# OptronV7_PCB.net
KiCad netlist of a schematic drawn in EAGLE
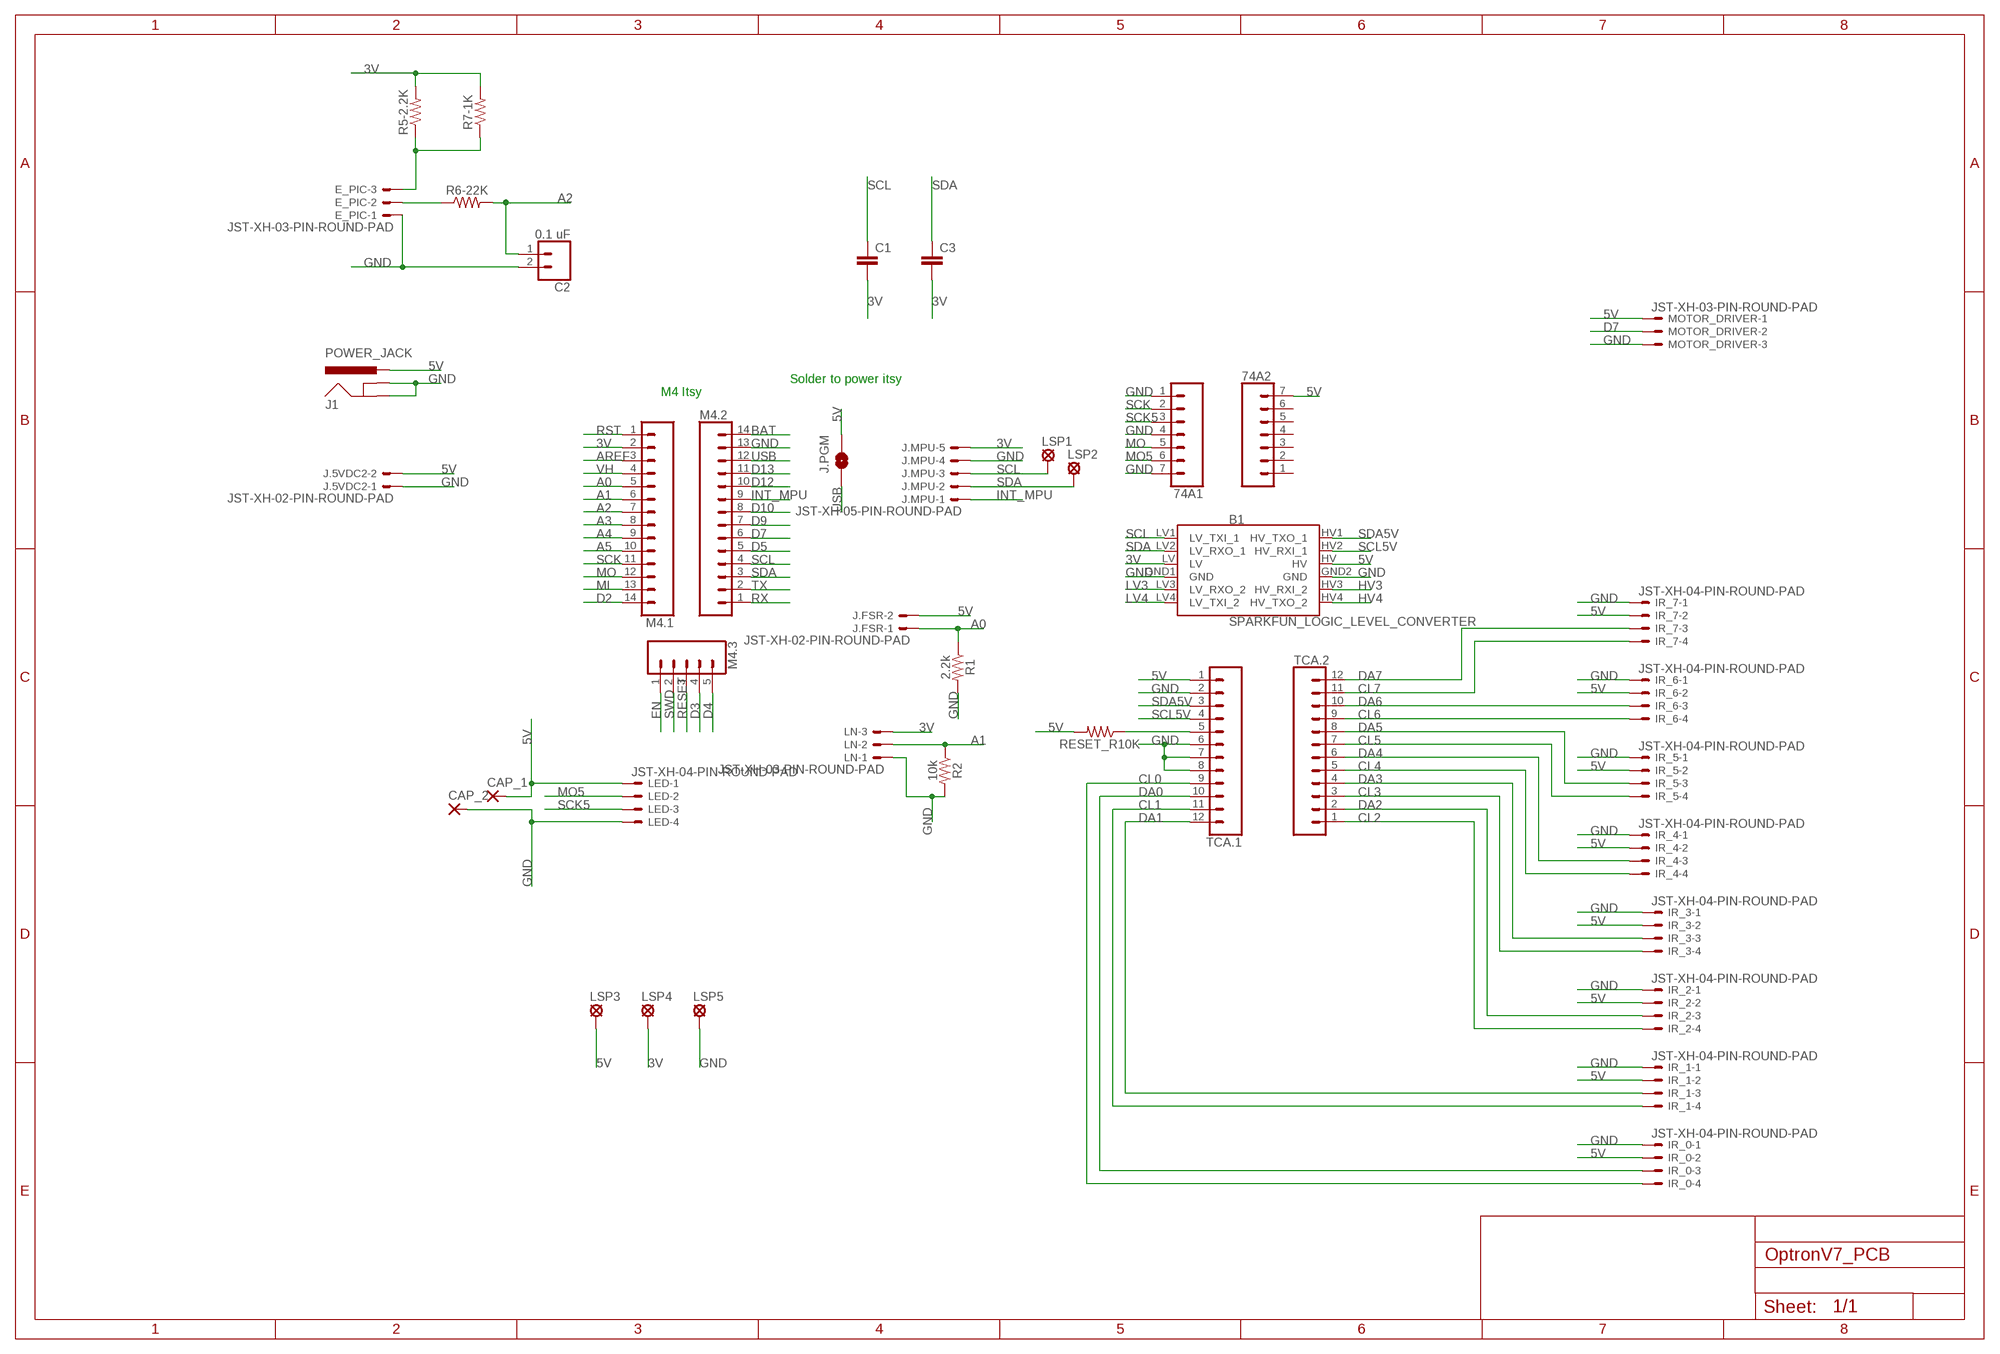
[diagram p0: schematic, sheet 1]

(export (version "E")
  (design (tool "Eeschema 10.0.6"))
  (components
    (comp (ref "74A1")
      (value "CONN_07")
      (footprint "eagle-import:1X07")
      (libsource (lib "eagle-import") (part "CONN_07"))
    )
    (comp (ref "74A2")
      (value "CONN_07")
      (footprint "eagle-import:1X07")
      (libsource (lib "eagle-import") (part "CONN_07"))
    )
    (comp (ref "B1")
      (value "SPARKFUN_LOGIC_LEVEL_CONVERTER")
      (footprint "eagle-import:SPARKFUN_LOGIC_LEVEL_CONVERTER")
      (libsource (lib "eagle-import") (part "SPARKFUN_LOGIC_LEVEL_CONVERTER"))
    )
    (comp (ref "C1")
      (value "C5/2.5")
      (footprint "eagle-import:C5B2.5")
      (libsource (lib "eagle-import") (part "C5/2.5"))
    )
    (comp (ref "C2")
      (value "0.1 uF")
      (footprint "eagle-import:1X02")
      (libsource (lib "eagle-import") (part "CONN_02"))
    )
    (comp (ref "C3")
      (value "C5/2.5")
      (footprint "eagle-import:C5B2.5")
      (libsource (lib "eagle-import") (part "C5/2.5"))
    )
    (comp (ref "CAP_1")
      (value "1,6/0,8")
      (footprint "eagle-import:1,6_0,8")
      (libsource (lib "eagle-import") (part "1,6/0,8"))
    )
    (comp (ref "CAP_2")
      (value "1,6/0,8")
      (footprint "eagle-import:1,6_0,8")
      (libsource (lib "eagle-import") (part "1,6/0,8"))
    )
    (comp (ref "E_PIC")
      (value "JST-XH-03-PIN-ROUND-PAD")
      (footprint "eagle-import:JST-XH-03-PACKAGE-ROUND-PAD")
      (libsource (lib "eagle-import") (part "JST-XH-03-PIN-ROUND-PAD"))
    )
    (comp (ref "IR_0")
      (value "JST-XH-04-PIN-ROUND-PAD")
      (footprint "eagle-import:JST-XH-04-PACKAGE-ROUND-PAD")
      (libsource (lib "eagle-import") (part "JST-XH-04-PIN-ROUND-PAD"))
    )
    (comp (ref "IR_1")
      (value "JST-XH-04-PIN-ROUND-PAD")
      (footprint "eagle-import:JST-XH-04-PACKAGE-ROUND-PAD")
      (libsource (lib "eagle-import") (part "JST-XH-04-PIN-ROUND-PAD"))
    )
    (comp (ref "IR_2")
      (value "JST-XH-04-PIN-ROUND-PAD")
      (footprint "eagle-import:JST-XH-04-PACKAGE-ROUND-PAD")
      (libsource (lib "eagle-import") (part "JST-XH-04-PIN-ROUND-PAD"))
    )
    (comp (ref "IR_3")
      (value "JST-XH-04-PIN-ROUND-PAD")
      (footprint "eagle-import:JST-XH-04-PACKAGE-ROUND-PAD")
      (libsource (lib "eagle-import") (part "JST-XH-04-PIN-ROUND-PAD"))
    )
    (comp (ref "IR_4")
      (value "JST-XH-04-PIN-ROUND-PAD")
      (footprint "eagle-import:JST-XH-04-PACKAGE-ROUND-PAD")
      (libsource (lib "eagle-import") (part "JST-XH-04-PIN-ROUND-PAD"))
    )
    (comp (ref "IR_5")
      (value "JST-XH-04-PIN-ROUND-PAD")
      (footprint "eagle-import:JST-XH-04-PACKAGE-ROUND-PAD")
      (libsource (lib "eagle-import") (part "JST-XH-04-PIN-ROUND-PAD"))
    )
    (comp (ref "IR_6")
      (value "JST-XH-04-PIN-ROUND-PAD")
      (footprint "eagle-import:JST-XH-04-PACKAGE-ROUND-PAD")
      (libsource (lib "eagle-import") (part "JST-XH-04-PIN-ROUND-PAD"))
    )
    (comp (ref "IR_7")
      (value "JST-XH-04-PIN-ROUND-PAD")
      (footprint "eagle-import:JST-XH-04-PACKAGE-ROUND-PAD")
      (libsource (lib "eagle-import") (part "JST-XH-04-PIN-ROUND-PAD"))
    )
    (comp (ref "J.5VDC2")
      (value "JST-XH-02-PIN-ROUND-PAD")
      (footprint "eagle-import:JST-XH-02-PACKAGE-ROUND-PAD")
      (libsource (lib "eagle-import") (part "JST-XH-02-PIN-ROUND-PAD"))
    )
    (comp (ref "J.FSR")
      (value "JST-XH-02-PIN-ROUND-PAD")
      (footprint "eagle-import:JST-XH-02-PACKAGE-ROUND-PAD")
      (libsource (lib "eagle-import") (part "JST-XH-02-PIN-ROUND-PAD"))
    )
    (comp (ref "J.MPU")
      (value "JST-XH-05-PIN-ROUND-PAD")
      (footprint "eagle-import:JST-XH-05-PACKAGE-ROUND-PAD")
      (libsource (lib "eagle-import") (part "JST-XH-05-PIN-ROUND-PAD"))
    )
    (comp (ref "J.PGM")
      (value "JUMPER-SMT_2_NO_NO-SILK")
      (footprint "eagle-import:SMT-JUMPER_2_NO_NO-SILK")
      (libsource (lib "eagle-import") (part "JUMPER-SMT_2_NO_NO-SILK"))
    )
    (comp (ref "J1")
      (value "POWER_JACK")
      (footprint "eagle-import:POWER_JACK_PTH")
      (libsource (lib "eagle-import") (part "POWER_JACK"))
    )
    (comp (ref "LED")
      (value "JST-XH-04-PIN-ROUND-PAD")
      (footprint "eagle-import:JST-XH-04-PACKAGE-ROUND-PAD")
      (libsource (lib "eagle-import") (part "JST-XH-04-PIN-ROUND-PAD"))
    )
    (comp (ref "LN")
      (value "JST-XH-03-PIN-ROUND-PAD")
      (footprint "eagle-import:JST-XH-03-PACKAGE-ROUND-PAD")
      (libsource (lib "eagle-import") (part "JST-XH-03-PIN-ROUND-PAD"))
    )
    (comp (ref "LSP1")
      (value "MCS08")
      (footprint "eagle-import:MCS08")
      (libsource (lib "eagle-import") (part "MCS08"))
    )
    (comp (ref "LSP2")
      (value "MCS08")
      (footprint "eagle-import:MCS08")
      (libsource (lib "eagle-import") (part "MCS08"))
    )
    (comp (ref "LSP3")
      (value "MCS08")
      (footprint "eagle-import:MCS08")
      (libsource (lib "eagle-import") (part "MCS08"))
    )
    (comp (ref "LSP4")
      (value "MCS08")
      (footprint "eagle-import:MCS08")
      (libsource (lib "eagle-import") (part "MCS08"))
    )
    (comp (ref "LSP5")
      (value "MCS08")
      (footprint "eagle-import:MCS08")
      (libsource (lib "eagle-import") (part "MCS08"))
    )
    (comp (ref "M4.1")
      (value "CONN_14")
      (footprint "eagle-import:1X14")
      (libsource (lib "eagle-import") (part "CONN_14"))
    )
    (comp (ref "M4.2")
      (value "CONN_14")
      (footprint "eagle-import:1X14")
      (libsource (lib "eagle-import") (part "CONN_14"))
    )
    (comp (ref "M4.3")
      (value "CONN_05")
      (footprint "eagle-import:1X05")
      (libsource (lib "eagle-import") (part "CONN_05"))
    )
    (comp (ref "MOTOR_DRIVER")
      (value "JST-XH-03-PIN-ROUND-PAD")
      (footprint "eagle-import:JST-XH-03-PACKAGE-ROUND-PAD")
      (libsource (lib "eagle-import") (part "JST-XH-03-PIN-ROUND-PAD"))
    )
    (comp (ref "R1")
      (value "2.2k")
      (footprint "eagle-import:AXIAL-0.3")
      (libsource (lib "eagle-import") (part "10KOHM-HORIZ-1/4W-5%"))
    )
    (comp (ref "R2")
      (value "10k")
      (footprint "eagle-import:AXIAL-0.3")
      (libsource (lib "eagle-import") (part "10KOHM-HORIZ-1/4W-5%"))
    )
    (comp (ref "R5-2.2K")
      (value "RESISTORAXIAL-0.3")
      (footprint "eagle-import:AXIAL-0.3")
      (libsource (lib "eagle-import") (part "RESISTORAXIAL-0.3"))
    )
    (comp (ref "R6-22K")
      (value "RESISTORAXIAL-0.3")
      (footprint "eagle-import:AXIAL-0.3")
      (libsource (lib "eagle-import") (part "RESISTORAXIAL-0.3"))
    )
    (comp (ref "R7-1K")
      (value "RESISTORAXIAL-0.3")
      (footprint "eagle-import:AXIAL-0.3")
      (libsource (lib "eagle-import") (part "RESISTORAXIAL-0.3"))
    )
    (comp (ref "RESET_R10K")
      (value "RESISTORAXIAL-0.3")
      (footprint "eagle-import:AXIAL-0.3")
      (libsource (lib "eagle-import") (part "RESISTORAXIAL-0.3"))
    )
    (comp (ref "TCA.1")
      (value "CONN_12")
      (footprint "eagle-import:1X12")
      (libsource (lib "eagle-import") (part "CONN_12"))
    )
    (comp (ref "TCA.2")
      (value "CONN_12")
      (footprint "eagle-import:1X12")
      (libsource (lib "eagle-import") (part "CONN_12"))
    )
  )
  (nets
    (net (code "1") (name "/3V") (class "Default")
      (node (ref "B1") (pin "LV") (pinfunction "LV_LV") (pintype "power_in"))
      (node (ref "C1") (pin "2") (pinfunction "2_2") (pintype "passive"))
      (node (ref "C3") (pin "2") (pinfunction "2_2") (pintype "passive"))
      (node (ref "J.MPU") (pin "5") (pinfunction "S_5") (pintype "passive"))
      (node (ref "LN") (pin "3") (pinfunction "S_3") (pintype "passive"))
      (node (ref "LSP4") (pin "MP") (pinfunction "MP_MP") (pintype "passive"))
      (node (ref "M4.1") (pin "2") (pinfunction "2_2") (pintype "passive"))
      (node (ref "R5-2.2K") (pin "P$2") (pinfunction "2_P$2") (pintype "passive"))
      (node (ref "R7-1K") (pin "P$2") (pinfunction "2_P$2") (pintype "passive"))
    )
    (net (code "2") (name "/5V") (class "Default")
      (node (ref "74A2") (pin "7") (pinfunction "7_7") (pintype "passive"))
      (node (ref "B1") (pin "HV") (pinfunction "HV_HV") (pintype "power_in"))
      (node (ref "CAP_1") (pin "1") (pinfunction "P_1") (pintype "passive"))
      (node (ref "IR_0") (pin "2") (pinfunction "S_2") (pintype "passive"))
      (node (ref "IR_1") (pin "2") (pinfunction "S_2") (pintype "passive"))
      (node (ref "IR_2") (pin "2") (pinfunction "S_2") (pintype "passive"))
      (node (ref "IR_3") (pin "2") (pinfunction "S_2") (pintype "passive"))
      (node (ref "IR_4") (pin "2") (pinfunction "S_2") (pintype "passive"))
      (node (ref "IR_5") (pin "2") (pinfunction "S_2") (pintype "passive"))
      (node (ref "IR_6") (pin "2") (pinfunction "S_2") (pintype "passive"))
      (node (ref "IR_7") (pin "2") (pinfunction "S_2") (pintype "passive"))
      (node (ref "J.5VDC2") (pin "2") (pinfunction "S_2") (pintype "passive"))
      (node (ref "J.FSR") (pin "2") (pinfunction "S_2") (pintype "passive"))
      (node (ref "J.PGM") (pin "2") (pinfunction "2_2") (pintype "passive"))
      (node (ref "J1") (pin "PWR") (pinfunction "PWR_PWR") (pintype "bidirectional"))
      (node (ref "LED") (pin "1") (pinfunction "S_1") (pintype "passive"))
      (node (ref "LSP3") (pin "MP") (pinfunction "MP_MP") (pintype "passive"))
      (node (ref "MOTOR_DRIVER") (pin "1") (pinfunction "S_1") (pintype "passive"))
      (node (ref "RESET_R10K") (pin "P$2") (pinfunction "2_P$2") (pintype "passive"))
      (node (ref "TCA.1") (pin "1") (pinfunction "1_1") (pintype "passive"))
    )
    (net (code "3") (name "/A0") (class "Default")
      (node (ref "J.FSR") (pin "1") (pinfunction "S_1") (pintype "passive"))
      (node (ref "M4.1") (pin "5") (pinfunction "5_5") (pintype "passive"))
      (node (ref "R1") (pin "P$1") (pinfunction "1_P$1") (pintype "passive"))
    )
    (net (code "4") (name "/A1") (class "Default")
      (node (ref "LN") (pin "2") (pinfunction "S_2") (pintype "passive"))
      (node (ref "M4.1") (pin "6") (pinfunction "6_6") (pintype "passive"))
      (node (ref "R2") (pin "P$1") (pinfunction "1_P$1") (pintype "passive"))
    )
    (net (code "5") (name "/A2") (class "Default")
      (node (ref "C2") (pin "1") (pinfunction "1_1") (pintype "passive"))
      (node (ref "M4.1") (pin "7") (pinfunction "7_7") (pintype "passive"))
      (node (ref "R6-22K") (pin "P$2") (pinfunction "2_P$2") (pintype "passive"))
    )
    (net (code "6") (name "/A3") (class "Default")
      (node (ref "M4.1") (pin "8") (pinfunction "8_8") (pintype "passive"))
    )
    (net (code "7") (name "/A4") (class "Default")
      (node (ref "M4.1") (pin "9") (pinfunction "9_9") (pintype "passive"))
    )
    (net (code "8") (name "/A5") (class "Default")
      (node (ref "M4.1") (pin "10") (pinfunction "10_10") (pintype "passive"))
    )
    (net (code "9") (name "/AREF") (class "Default")
      (node (ref "M4.1") (pin "3") (pinfunction "3_3") (pintype "passive"))
    )
    (net (code "10") (name "/BAT") (class "Default")
      (node (ref "M4.2") (pin "14") (pinfunction "14_14") (pintype "passive"))
    )
    (net (code "11") (name "/CL0") (class "Default")
      (node (ref "IR_0") (pin "4") (pinfunction "S_4") (pintype "passive"))
      (node (ref "TCA.1") (pin "9") (pinfunction "9_9") (pintype "passive"))
    )
    (net (code "12") (name "/CL1") (class "Default")
      (node (ref "IR_1") (pin "4") (pinfunction "S_4") (pintype "passive"))
      (node (ref "TCA.1") (pin "11") (pinfunction "11_11") (pintype "passive"))
    )
    (net (code "13") (name "/CL2") (class "Default")
      (node (ref "IR_2") (pin "4") (pinfunction "S_4") (pintype "passive"))
      (node (ref "TCA.2") (pin "1") (pinfunction "1_1") (pintype "passive"))
    )
    (net (code "14") (name "/CL3") (class "Default")
      (node (ref "IR_3") (pin "4") (pinfunction "S_4") (pintype "passive"))
      (node (ref "TCA.2") (pin "3") (pinfunction "3_3") (pintype "passive"))
    )
    (net (code "15") (name "/CL4") (class "Default")
      (node (ref "IR_4") (pin "4") (pinfunction "S_4") (pintype "passive"))
      (node (ref "TCA.2") (pin "5") (pinfunction "5_5") (pintype "passive"))
    )
    (net (code "16") (name "/CL5") (class "Default")
      (node (ref "IR_5") (pin "4") (pinfunction "S_4") (pintype "passive"))
      (node (ref "TCA.2") (pin "7") (pinfunction "7_7") (pintype "passive"))
    )
    (net (code "17") (name "/CL6") (class "Default")
      (node (ref "IR_6") (pin "4") (pinfunction "S_4") (pintype "passive"))
      (node (ref "TCA.2") (pin "9") (pinfunction "9_9") (pintype "passive"))
    )
    (net (code "18") (name "/CL7") (class "Default")
      (node (ref "IR_7") (pin "4") (pinfunction "S_4") (pintype "passive"))
      (node (ref "TCA.2") (pin "11") (pinfunction "11_11") (pintype "passive"))
    )
    (net (code "19") (name "/D2") (class "Default")
      (node (ref "M4.1") (pin "14") (pinfunction "14_14") (pintype "passive"))
    )
    (net (code "20") (name "/D3") (class "Default")
      (node (ref "M4.3") (pin "4") (pinfunction "4_4") (pintype "passive"))
    )
    (net (code "21") (name "/D4") (class "Default")
      (node (ref "M4.3") (pin "5") (pinfunction "5_5") (pintype "passive"))
    )
    (net (code "22") (name "/D5") (class "Default")
      (node (ref "M4.2") (pin "5") (pinfunction "5_5") (pintype "passive"))
    )
    (net (code "23") (name "/D7") (class "Default")
      (node (ref "M4.2") (pin "6") (pinfunction "6_6") (pintype "passive"))
      (node (ref "MOTOR_DRIVER") (pin "2") (pinfunction "S_2") (pintype "passive"))
    )
    (net (code "24") (name "/D9") (class "Default")
      (node (ref "M4.2") (pin "7") (pinfunction "7_7") (pintype "passive"))
    )
    (net (code "25") (name "/D10") (class "Default")
      (node (ref "M4.2") (pin "8") (pinfunction "8_8") (pintype "passive"))
    )
    (net (code "26") (name "/D12") (class "Default")
      (node (ref "M4.2") (pin "10") (pinfunction "10_10") (pintype "passive"))
    )
    (net (code "27") (name "/D13") (class "Default")
      (node (ref "M4.2") (pin "11") (pinfunction "11_11") (pintype "passive"))
    )
    (net (code "28") (name "/DA0") (class "Default")
      (node (ref "IR_0") (pin "3") (pinfunction "S_3") (pintype "passive"))
      (node (ref "TCA.1") (pin "10") (pinfunction "10_10") (pintype "passive"))
    )
    (net (code "29") (name "/DA1") (class "Default")
      (node (ref "IR_1") (pin "3") (pinfunction "S_3") (pintype "passive"))
      (node (ref "TCA.1") (pin "12") (pinfunction "12_12") (pintype "passive"))
    )
    (net (code "30") (name "/DA2") (class "Default")
      (node (ref "IR_2") (pin "3") (pinfunction "S_3") (pintype "passive"))
      (node (ref "TCA.2") (pin "2") (pinfunction "2_2") (pintype "passive"))
    )
    (net (code "31") (name "/DA3") (class "Default")
      (node (ref "IR_3") (pin "3") (pinfunction "S_3") (pintype "passive"))
      (node (ref "TCA.2") (pin "4") (pinfunction "4_4") (pintype "passive"))
    )
    (net (code "32") (name "/DA4") (class "Default")
      (node (ref "IR_4") (pin "3") (pinfunction "S_3") (pintype "passive"))
      (node (ref "TCA.2") (pin "6") (pinfunction "6_6") (pintype "passive"))
    )
    (net (code "33") (name "/DA5") (class "Default")
      (node (ref "IR_5") (pin "3") (pinfunction "S_3") (pintype "passive"))
      (node (ref "TCA.2") (pin "8") (pinfunction "8_8") (pintype "passive"))
    )
    (net (code "34") (name "/DA6") (class "Default")
      (node (ref "IR_6") (pin "3") (pinfunction "S_3") (pintype "passive"))
      (node (ref "TCA.2") (pin "10") (pinfunction "10_10") (pintype "passive"))
    )
    (net (code "35") (name "/DA7") (class "Default")
      (node (ref "IR_7") (pin "3") (pinfunction "S_3") (pintype "passive"))
      (node (ref "TCA.2") (pin "12") (pinfunction "12_12") (pintype "passive"))
    )
    (net (code "36") (name "/EN") (class "Default")
      (node (ref "M4.3") (pin "1") (pinfunction "1_1") (pintype "passive"))
    )
    (net (code "37") (name "/GND") (class "Default")
      (node (ref "74A1") (pin "1") (pinfunction "1_1") (pintype "passive"))
      (node (ref "74A1") (pin "4") (pinfunction "4_4") (pintype "passive"))
      (node (ref "74A1") (pin "7") (pinfunction "7_7") (pintype "passive"))
      (node (ref "B1") (pin "GND1") (pinfunction "GND_GND1") (pintype "power_in"))
      (node (ref "B1") (pin "GND2") (pinfunction "GND_GND2") (pintype "power_in"))
      (node (ref "C2") (pin "2") (pinfunction "2_2") (pintype "passive"))
      (node (ref "CAP_2") (pin "1") (pinfunction "P_1") (pintype "passive"))
      (node (ref "E_PIC") (pin "1") (pinfunction "S_1") (pintype "passive"))
      (node (ref "IR_0") (pin "1") (pinfunction "S_1") (pintype "passive"))
      (node (ref "IR_1") (pin "1") (pinfunction "S_1") (pintype "passive"))
      (node (ref "IR_2") (pin "1") (pinfunction "S_1") (pintype "passive"))
      (node (ref "IR_3") (pin "1") (pinfunction "S_1") (pintype "passive"))
      (node (ref "IR_4") (pin "1") (pinfunction "S_1") (pintype "passive"))
      (node (ref "IR_5") (pin "1") (pinfunction "S_1") (pintype "passive"))
      (node (ref "IR_6") (pin "1") (pinfunction "S_1") (pintype "passive"))
      (node (ref "IR_7") (pin "1") (pinfunction "S_1") (pintype "passive"))
      (node (ref "J.5VDC2") (pin "1") (pinfunction "S_1") (pintype "passive"))
      (node (ref "J.MPU") (pin "4") (pinfunction "S_4") (pintype "passive"))
      (node (ref "J1") (pin "GND") (pinfunction "GND_GND") (pintype "bidirectional"))
      (node (ref "J1") (pin "GNDBREAK") (pinfunction "GNDBREAK_GNDBREAK") (pintype "bidirectional"))
      (node (ref "LED") (pin "4") (pinfunction "S_4") (pintype "passive"))
      (node (ref "LN") (pin "1") (pinfunction "S_1") (pintype "passive"))
      (node (ref "LSP5") (pin "MP") (pinfunction "MP_MP") (pintype "passive"))
      (node (ref "M4.2") (pin "13") (pinfunction "13_13") (pintype "passive"))
      (node (ref "MOTOR_DRIVER") (pin "3") (pinfunction "S_3") (pintype "passive"))
      (node (ref "R1") (pin "P$2") (pinfunction "2_P$2") (pintype "passive"))
      (node (ref "R2") (pin "P$2") (pinfunction "2_P$2") (pintype "passive"))
      (node (ref "TCA.1") (pin "2") (pinfunction "2_2") (pintype "passive"))
      (node (ref "TCA.1") (pin "6") (pinfunction "6_6") (pintype "passive"))
      (node (ref "TCA.1") (pin "7") (pinfunction "7_7") (pintype "passive"))
      (node (ref "TCA.1") (pin "8") (pinfunction "8_8") (pintype "passive"))
    )
    (net (code "38") (name "/HV3") (class "Default")
      (node (ref "B1") (pin "HV3") (pinfunction "HV_RXI_2_HV3") (pintype "bidirectional"))
    )
    (net (code "39") (name "/HV4") (class "Default")
      (node (ref "B1") (pin "HV4") (pinfunction "HV_TXO_2_HV4") (pintype "bidirectional"))
    )
    (net (code "40") (name "/INT_MPU") (class "Default")
      (node (ref "J.MPU") (pin "1") (pinfunction "S_1") (pintype "passive"))
      (node (ref "M4.2") (pin "9") (pinfunction "9_9") (pintype "passive"))
    )
    (net (code "41") (name "/LV3") (class "Default")
      (node (ref "B1") (pin "LV3") (pinfunction "LV_RXO_2_LV3") (pintype "bidirectional"))
    )
    (net (code "42") (name "/LV4") (class "Default")
      (node (ref "B1") (pin "LV4") (pinfunction "LV_TXI_2_LV4") (pintype "bidirectional"))
    )
    (net (code "43") (name "/MI") (class "Default")
      (node (ref "M4.1") (pin "13") (pinfunction "13_13") (pintype "passive"))
    )
    (net (code "44") (name "/MO") (class "Default")
      (node (ref "74A1") (pin "5") (pinfunction "5_5") (pintype "passive"))
      (node (ref "M4.1") (pin "12") (pinfunction "12_12") (pintype "passive"))
    )
    (net (code "45") (name "/MO5") (class "Default")
      (node (ref "74A1") (pin "6") (pinfunction "6_6") (pintype "passive"))
      (node (ref "LED") (pin "2") (pinfunction "S_2") (pintype "passive"))
    )
    (net (code "46") (name "/RESET") (class "Default")
      (node (ref "M4.3") (pin "3") (pinfunction "3_3") (pintype "passive"))
    )
    (net (code "47") (name "/RST") (class "Default")
      (node (ref "M4.1") (pin "1") (pinfunction "1_1") (pintype "passive"))
    )
    (net (code "48") (name "/RX") (class "Default")
      (node (ref "M4.2") (pin "1") (pinfunction "1_1") (pintype "passive"))
    )
    (net (code "49") (name "/SCK") (class "Default")
      (node (ref "74A1") (pin "2") (pinfunction "2_2") (pintype "passive"))
      (node (ref "M4.1") (pin "11") (pinfunction "11_11") (pintype "passive"))
    )
    (net (code "50") (name "/SCK5") (class "Default")
      (node (ref "74A1") (pin "3") (pinfunction "3_3") (pintype "passive"))
      (node (ref "LED") (pin "3") (pinfunction "S_3") (pintype "passive"))
    )
    (net (code "51") (name "/SCL") (class "Default")
      (node (ref "B1") (pin "LV1") (pinfunction "LV_TXI_1_LV1") (pintype "bidirectional"))
      (node (ref "C1") (pin "1") (pinfunction "1_1") (pintype "passive"))
      (node (ref "J.MPU") (pin "3") (pinfunction "S_3") (pintype "passive"))
      (node (ref "LSP1") (pin "MP") (pinfunction "MP_MP") (pintype "passive"))
      (node (ref "M4.2") (pin "4") (pinfunction "4_4") (pintype "passive"))
    )
    (net (code "52") (name "/SCL5V") (class "Default")
      (node (ref "B1") (pin "HV2") (pinfunction "HV_RXI_1_HV2") (pintype "bidirectional"))
      (node (ref "TCA.1") (pin "4") (pinfunction "4_4") (pintype "passive"))
    )
    (net (code "53") (name "/SDA") (class "Default")
      (node (ref "B1") (pin "LV2") (pinfunction "LV_RXO_1_LV2") (pintype "bidirectional"))
      (node (ref "C3") (pin "1") (pinfunction "1_1") (pintype "passive"))
      (node (ref "J.MPU") (pin "2") (pinfunction "S_2") (pintype "passive"))
      (node (ref "LSP2") (pin "MP") (pinfunction "MP_MP") (pintype "passive"))
      (node (ref "M4.2") (pin "3") (pinfunction "3_3") (pintype "passive"))
    )
    (net (code "54") (name "/SDA5V") (class "Default")
      (node (ref "B1") (pin "HV1") (pinfunction "HV_TXO_1_HV1") (pintype "bidirectional"))
      (node (ref "TCA.1") (pin "3") (pinfunction "3_3") (pintype "passive"))
    )
    (net (code "55") (name "/SWD") (class "Default")
      (node (ref "M4.3") (pin "2") (pinfunction "2_2") (pintype "passive"))
    )
    (net (code "56") (name "/TX") (class "Default")
      (node (ref "M4.2") (pin "2") (pinfunction "2_2") (pintype "passive"))
    )
    (net (code "57") (name "/USB") (class "Default")
      (node (ref "J.PGM") (pin "1") (pinfunction "1_1") (pintype "passive"))
      (node (ref "M4.2") (pin "12") (pinfunction "12_12") (pintype "passive"))
    )
    (net (code "58") (name "/VH") (class "Default")
      (node (ref "M4.1") (pin "4") (pinfunction "4_4") (pintype "passive"))
    )
    (net (code "59") (name "Net-(E_PICB-S)") (class "Default")
      (node (ref "E_PIC") (pin "2") (pinfunction "S_2") (pintype "passive"))
      (node (ref "R6-22K") (pin "P$1") (pinfunction "1_P$1") (pintype "passive"))
    )
    (net (code "60") (name "Net-(E_PICC-S)") (class "Default")
      (node (ref "E_PIC") (pin "3") (pinfunction "S_3") (pintype "passive"))
      (node (ref "R5-2.2K") (pin "P$1") (pinfunction "1_P$1") (pintype "passive"))
      (node (ref "R7-1K") (pin "P$1") (pinfunction "1_P$1") (pintype "passive"))
    )
    (net (code "61") (name "Net-(RESET_R10K-1)") (class "Default")
      (node (ref "RESET_R10K") (pin "P$1") (pinfunction "1_P$1") (pintype "passive"))
      (node (ref "TCA.1") (pin "5") (pinfunction "5_5") (pintype "passive"))
    )
    (net (code "62") (name "unconnected-(74A2-Pad1)") (class "Default")
      (node (ref "74A2") (pin "1") (pinfunction "1_1") (pintype "passive"))
    )
    (net (code "63") (name "unconnected-(74A2-Pad2)") (class "Default")
      (node (ref "74A2") (pin "2") (pinfunction "2_2") (pintype "passive"))
    )
    (net (code "64") (name "unconnected-(74A2-Pad3)") (class "Default")
      (node (ref "74A2") (pin "3") (pinfunction "3_3") (pintype "passive"))
    )
    (net (code "65") (name "unconnected-(74A2-Pad4)") (class "Default")
      (node (ref "74A2") (pin "4") (pinfunction "4_4") (pintype "passive"))
    )
    (net (code "66") (name "unconnected-(74A2-Pad5)") (class "Default")
      (node (ref "74A2") (pin "5") (pinfunction "5_5") (pintype "passive"))
    )
    (net (code "67") (name "unconnected-(74A2-Pad6)") (class "Default")
      (node (ref "74A2") (pin "6") (pinfunction "6_6") (pintype "passive"))
    )
  )
)
